# 1_P1.net
KiCad netlist of a schematic drawn in Altium Designer
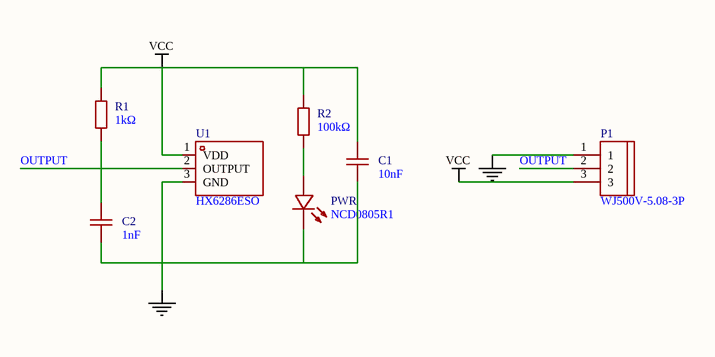
[diagram p0: 1_P1.schdoc]

(export (version "E")
  (design (tool "Eeschema 10.0.6"))
  (components
    (comp (ref "C1")
      (value "10nF")
      (footprint "C0603")
      (fields
        (field (name "MANUFACTURER") "YAGEO(国巨)")
        (field (name "MANUFACTURER PART") "CC0603KRX7R9BB103")
        (field (name "TOLERANCE") "±10%")
      )
      (libsource (lib "altium-import") (part "root_1_CC0603KRX7R9BB103_"))
    )
    (comp (ref "C2")
      (value "1nF")
      (footprint "C0603")
      (fields
        (field (name "MANUFACTURER") "SAMSUNG(三星)")
        (field (name "MANUFACTURER PART") "CL10B102KB8NNNC")
        (field (name "TOLERANCE") "±10%")
      )
      (libsource (lib "altium-import") (part "root_1_CL10B102KB8NNNC_"))
    )
    (comp (ref "P1")
      (value "WJ500V-5.08-3P")
      (footprint "CONN-TH_3P-P5.00_WJ500V-5.08-3P")
      (fields (field (name "MANUFACTURER") "KANGNEX(康奈克斯电气)"))
      (libsource (lib "altium-import") (part "root_3_WJ500V-5.08-3P_"))
    )
    (comp (ref "PWR")
      (value "NCD0805R1")
      (footprint "LED0805-R-RD")
      (fields (field (name "MANUFACTURER") "国星光电"))
      (libsource (lib "altium-import") (part "root_1_mirrored_NCD0805R1_"))
    )
    (comp (ref "R1")
      (value "1kΩ")
      (footprint "R0603")
      (fields
        (field (name "MANUFACTURER") "YAGEO(国巨)")
        (field (name "MANUFACTURER PART") "RT0603BRD071KL")
        (field (name "TOLERANCE") "±0.1%")
      )
      (libsource (lib "altium-import") (part "root_1_RT0603BRD071KL_"))
    )
    (comp (ref "R2")
      (value "100kΩ")
      (footprint "R0603")
      (fields
        (field (name "MANUFACTURER") "YAGEO(国巨)")
        (field (name "MANUFACTURER PART") "RC0603FR-07100KL")
        (field (name "TOLERANCE") "±1%")
      )
      (libsource (lib "altium-import") (part "root_1_RC0603FR-07100KL_"))
    )
    (comp (ref "U1")
      (value "HX6286ESO")
      (footprint "SOT-23-3_L2.9-W1.6-P1.90-LS2.8-BR")
      (fields (field (name "MANUFACTURER") "HUAXIN(华芯)"))
      (libsource (lib "altium-import") (part "root_0_HX6286ESO_"))
    )
  )
  (nets
    (net (code "1") (name "/OUTPUT") (class "Default")
      (node (ref "C2") (pin "2") (pinfunction "2_2") (pintype "passive"))
      (node (ref "P1") (pin "2") (pinfunction "2_2") (pintype "passive"))
      (node (ref "R1") (pin "1") (pinfunction "1_1") (pintype "passive"))
      (node (ref "U1") (pin "2") (pinfunction "OUTPUT_2") (pintype "passive"))
    )
    (net (code "2") (name "GND") (class "Default")
      (node (ref "C1") (pin "1") (pinfunction "1_1") (pintype "passive"))
      (node (ref "C2") (pin "1") (pinfunction "1_1") (pintype "passive"))
      (node (ref "P1") (pin "1") (pinfunction "1_1") (pintype "passive"))
      (node (ref "PWR") (pin "2") (pinfunction "-_2") (pintype "passive"))
      (node (ref "U1") (pin "3") (pinfunction "GND_3") (pintype "passive"))
    )
    (net (code "3") (name "Net-(PWR-+)") (class "Default")
      (node (ref "PWR") (pin "1") (pinfunction "+_1") (pintype "passive"))
      (node (ref "R2") (pin "1") (pinfunction "1_1") (pintype "passive"))
    )
    (net (code "4") (name "VCC") (class "Default")
      (node (ref "C1") (pin "2") (pinfunction "2_2") (pintype "passive"))
      (node (ref "P1") (pin "3") (pinfunction "3_3") (pintype "passive"))
      (node (ref "R1") (pin "2") (pinfunction "2_2") (pintype "passive"))
      (node (ref "R2") (pin "2") (pinfunction "2_2") (pintype "passive"))
      (node (ref "U1") (pin "1") (pinfunction "VDD_1") (pintype "passive"))
    )
  )
)
